# sensor.net
KiCad netlist of a schematic drawn in EAGLE
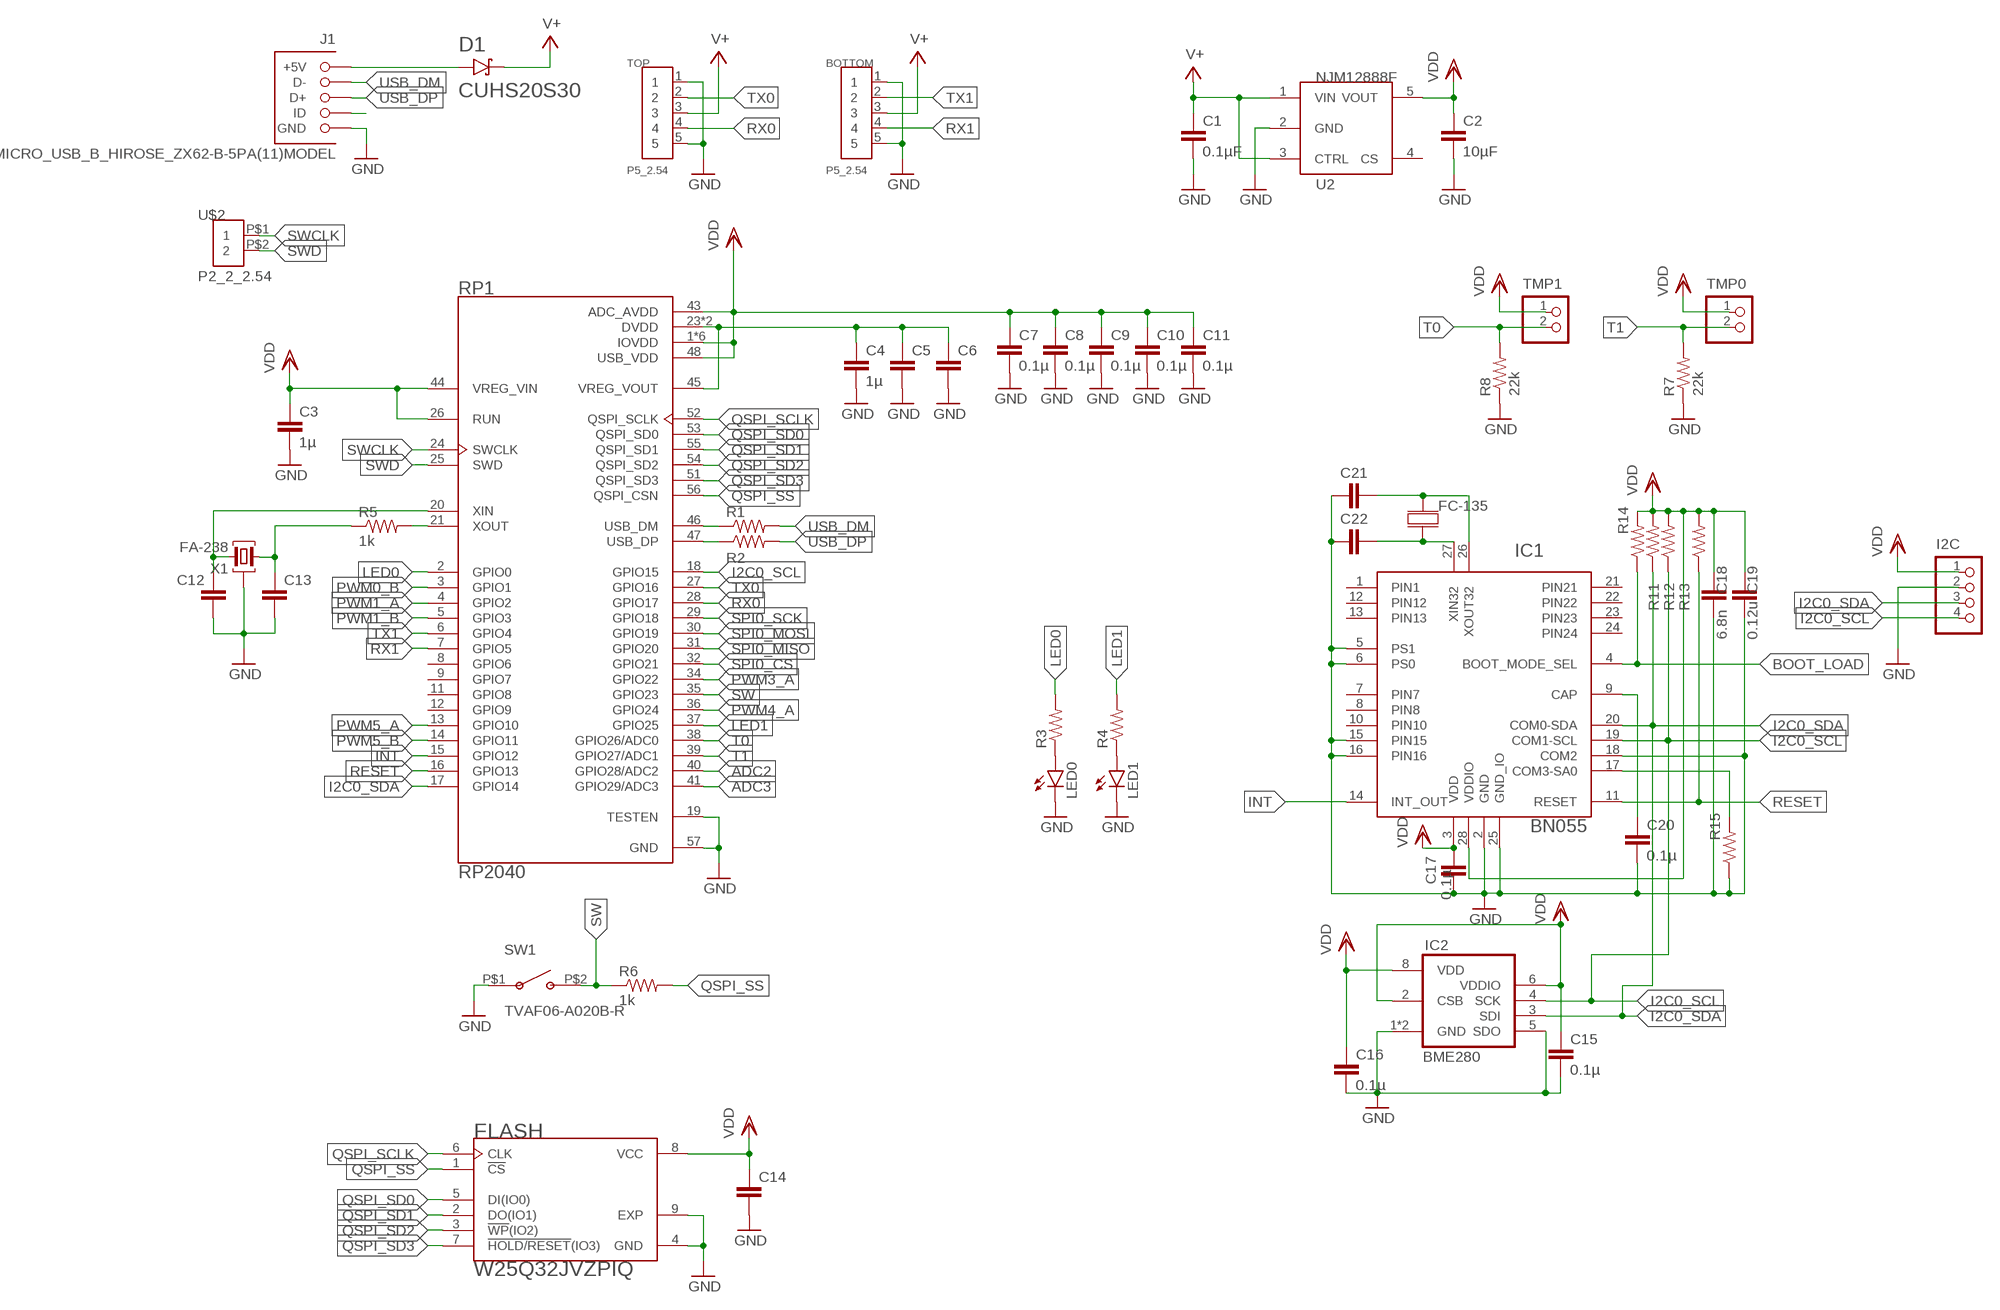
[diagram p0: schematic, sheet 1]

(export (version "E")
  (design (tool "Eeschema 10.0.6"))
  (components
    (comp (ref "BOTTOM")
      (value "P5_2.54")
      (footprint "eagle-import:P5_2.54")
      (libsource (lib "eagle-import") (part "P5_2.54"))
    )
    (comp (ref "C1")
      (value "0.1µF")
      (footprint "eagle-import:C0402")
      (libsource (lib "eagle-import") (part "C-EUC0402"))
    )
    (comp (ref "C2")
      (value "10µF")
      (footprint "eagle-import:C0402")
      (libsource (lib "eagle-import") (part "C-EUC0402"))
    )
    (comp (ref "C3")
      (value "1µ")
      (footprint "eagle-import:C0402")
      (libsource (lib "eagle-import") (part "C-EUC0402"))
    )
    (comp (ref "C4")
      (value "1µ")
      (footprint "eagle-import:C0402")
      (libsource (lib "eagle-import") (part "C-EUC0402"))
    )
    (comp (ref "C5")
      (value "C-EUC0402")
      (footprint "eagle-import:C0402")
      (libsource (lib "eagle-import") (part "C-EUC0402"))
    )
    (comp (ref "C6")
      (value "C-EUC0402")
      (footprint "eagle-import:C0402")
      (libsource (lib "eagle-import") (part "C-EUC0402"))
    )
    (comp (ref "C7")
      (value "0.1µ")
      (footprint "eagle-import:C0402")
      (libsource (lib "eagle-import") (part "C-EUC0402"))
    )
    (comp (ref "C8")
      (value "0.1µ")
      (footprint "eagle-import:C0402")
      (libsource (lib "eagle-import") (part "C-EUC0402"))
    )
    (comp (ref "C9")
      (value "0.1µ")
      (footprint "eagle-import:C0402")
      (libsource (lib "eagle-import") (part "C-EUC0402"))
    )
    (comp (ref "C10")
      (value "0.1µ")
      (footprint "eagle-import:C0402")
      (libsource (lib "eagle-import") (part "C-EUC0402"))
    )
    (comp (ref "C11")
      (value "0.1µ")
      (footprint "eagle-import:C0402")
      (libsource (lib "eagle-import") (part "C-EUC0402"))
    )
    (comp (ref "C12")
      (value "C-EUC0402")
      (footprint "eagle-import:C0402")
      (libsource (lib "eagle-import") (part "C-EUC0402"))
    )
    (comp (ref "C13")
      (value "C-EUC0402")
      (footprint "eagle-import:C0402")
      (libsource (lib "eagle-import") (part "C-EUC0402"))
    )
    (comp (ref "C14")
      (value "C-EUC0402")
      (footprint "eagle-import:C0402")
      (libsource (lib "eagle-import") (part "C-EUC0402"))
    )
    (comp (ref "C15")
      (value "0.1µ")
      (footprint "eagle-import:C0402")
      (libsource (lib "eagle-import") (part "C-EUC0402"))
    )
    (comp (ref "C16")
      (value "0.1µ")
      (footprint "eagle-import:C0402")
      (libsource (lib "eagle-import") (part "C-EUC0402"))
    )
    (comp (ref "C17")
      (value "0.1µ")
      (footprint "eagle-import:C0402")
      (libsource (lib "eagle-import") (part "C-EUC0402"))
    )
    (comp (ref "C18")
      (value "6.8n")
      (footprint "eagle-import:C0402")
      (libsource (lib "eagle-import") (part "C-EUC0402"))
    )
    (comp (ref "C19")
      (value "0.12u")
      (footprint "eagle-import:C0402")
      (libsource (lib "eagle-import") (part "C-EUC0402"))
    )
    (comp (ref "C20")
      (value "0.1µ")
      (footprint "eagle-import:C0402")
      (libsource (lib "eagle-import") (part "C-EUC0402"))
    )
    (comp (ref "C21")
      (value "C-EUC0402")
      (footprint "eagle-import:C0402")
      (libsource (lib "eagle-import") (part "C-EUC0402"))
    )
    (comp (ref "C22")
      (value "C-EUC0402")
      (footprint "eagle-import:C0402")
      (libsource (lib "eagle-import") (part "C-EUC0402"))
    )
    (comp (ref "D1")
      (value "CUHS20S30")
      (footprint "eagle-import:CUHS20S30")
      (libsource (lib "eagle-import") (part "CUHS20S30"))
    )
    (comp (ref "FC-135")
      (value "FC-135")
      (footprint "eagle-import:FC-135")
      (libsource (lib "eagle-import") (part "FC-135"))
    )
    (comp (ref "FLASH")
      (value "W25Q32JVZPIQ")
      (footprint "eagle-import:SON127P600X500X80-9N")
      (fields (field (name "MF") "Winbond"))
      (libsource (lib "eagle-import") (part "W25Q32JVZPIQ"))
    )
    (comp (ref "I2C")
      (value "B4B-PH-K-S")
      (footprint "eagle-import:B4B-PH-K-S")
      (libsource (lib "eagle-import") (part "B4B-PH-K-S"))
    )
    (comp (ref "IC1")
      (value "BN055")
      (footprint "eagle-import:LGA-28_3.80X5.20_0.5")
      (fields (field (name "PART_NUMBER") "BNO055"))
      (libsource (lib "eagle-import") (part "1658_BNO055"))
    )
    (comp (ref "IC2")
      (value "BME280")
      (footprint "eagle-import:BME280")
      (libsource (lib "eagle-import") (part "BME280"))
    )
    (comp (ref "J1")
      (value "MICRO_USB_B_HIROSE_ZX62-B-5PA(11)MODEL")
      (footprint "eagle-import:GHI-CONNECTORS_10118192-0001LF(MICRO-USB-B-AMPHENOL-FCI)")
      (libsource (lib "eagle-import") (part "MICRO_USB_B_HIROSE_ZX62-B-5PA(11)MODEL"))
    )
    (comp (ref "LED0")
      (value "LEDCHIPLED_0603")
      (footprint "eagle-import:CHIPLED_0603")
      (libsource (lib "eagle-import") (part "LEDCHIPLED_0603"))
    )
    (comp (ref "LED1")
      (value "LEDCHIPLED_0603")
      (footprint "eagle-import:CHIPLED_0603")
      (libsource (lib "eagle-import") (part "LEDCHIPLED_0603"))
    )
    (comp (ref "R1")
      (value "R-US_R0402")
      (footprint "eagle-import:R0402")
      (libsource (lib "eagle-import") (part "R-US_R0402"))
    )
    (comp (ref "R2")
      (value "R-US_R0402")
      (footprint "eagle-import:R0402")
      (libsource (lib "eagle-import") (part "R-US_R0402"))
    )
    (comp (ref "R3")
      (value "R-US_R0402")
      (footprint "eagle-import:R0402")
      (libsource (lib "eagle-import") (part "R-US_R0402"))
    )
    (comp (ref "R4")
      (value "R-US_R0402")
      (footprint "eagle-import:R0402")
      (libsource (lib "eagle-import") (part "R-US_R0402"))
    )
    (comp (ref "R5")
      (value "1k")
      (footprint "eagle-import:R0402")
      (libsource (lib "eagle-import") (part "R-US_R0402"))
    )
    (comp (ref "R6")
      (value "1k")
      (footprint "eagle-import:R0402")
      (libsource (lib "eagle-import") (part "R-US_R0402"))
    )
    (comp (ref "R7")
      (value "22k")
      (footprint "eagle-import:R0402")
      (libsource (lib "eagle-import") (part "R-US_R0402"))
    )
    (comp (ref "R8")
      (value "22k")
      (footprint "eagle-import:R0402")
      (libsource (lib "eagle-import") (part "R-US_R0402"))
    )
    (comp (ref "R11")
      (value "R-US_R0402")
      (footprint "eagle-import:R0402")
      (libsource (lib "eagle-import") (part "R-US_R0402"))
    )
    (comp (ref "R12")
      (value "R-US_R0402")
      (footprint "eagle-import:R0402")
      (libsource (lib "eagle-import") (part "R-US_R0402"))
    )
    (comp (ref "R13")
      (value "R-US_R0402")
      (footprint "eagle-import:R0402")
      (libsource (lib "eagle-import") (part "R-US_R0402"))
    )
    (comp (ref "R14")
      (value "R-US_R0402")
      (footprint "eagle-import:R0402")
      (libsource (lib "eagle-import") (part "R-US_R0402"))
    )
    (comp (ref "R15")
      (value "R-US_R0402")
      (footprint "eagle-import:R0402")
      (libsource (lib "eagle-import") (part "R-US_R0402"))
    )
    (comp (ref "RP1")
      (value "RP2040")
      (footprint "eagle-import:QFN40P700X700X90-57N")
      (fields (field (name "MF") "Raspberry Pi"))
      (libsource (lib "eagle-import") (part "RP2040"))
    )
    (comp (ref "SW1")
      (value "TVAF06-A020B-R")
      (footprint "eagle-import:TVAF06-A020B-R")
      (libsource (lib "eagle-import") (part "TVAF06-A020B-R"))
    )
    (comp (ref "TMP0")
      (value "S2B-PH-K-S")
      (footprint "eagle-import:S2B-PH-K-S")
      (libsource (lib "eagle-import") (part "S2B-PH-K-S"))
    )
    (comp (ref "TMP1")
      (value "S2B-PH-K-S")
      (footprint "eagle-import:S2B-PH-K-S")
      (libsource (lib "eagle-import") (part "S2B-PH-K-S"))
    )
    (comp (ref "TOP")
      (value "P5_2.54")
      (footprint "eagle-import:P5_2.54")
      (libsource (lib "eagle-import") (part "P5_2.54"))
    )
    (comp (ref "U$2")
      (value "P2_2_2.54")
      (footprint "eagle-import:P2_2.54")
      (libsource (lib "eagle-import") (part "P2_2_2.54"))
    )
    (comp (ref "U2")
      (value "NJM12888F")
      (footprint "eagle-import:SOT95P240X110-5N")
      (libsource (lib "eagle-import") (part "NJM12888F"))
    )
    (comp (ref "X1")
      (value "FA-238")
      (footprint "eagle-import:FA-238")
      (libsource (lib "eagle-import") (part "FA-238"))
    )
  )
  (nets
    (net (code "1") (name "ADC2") (class "Default")
      (node (ref "RP1") (pin "40") (pinfunction "GPIO28/ADC2_40") (pintype "bidirectional"))
    )
    (net (code "2") (name "ADC3") (class "Default")
      (node (ref "RP1") (pin "41") (pinfunction "GPIO29/ADC3_41") (pintype "bidirectional"))
    )
    (net (code "3") (name "BOOT_LOAD") (class "Default")
      (node (ref "IC1") (pin "4") (pinfunction "BOOT_MODE_SEL_4") (pintype "input"))
      (node (ref "R14") (pin "1") (pinfunction "1_1") (pintype "passive"))
    )
    (net (code "4") (name "GND") (class "Default")
      (node (ref "BOTTOM") (pin "1") (pinfunction "1_1") (pintype "bidirectional"))
      (node (ref "BOTTOM") (pin "5") (pinfunction "5_5") (pintype "bidirectional"))
      (node (ref "C1") (pin "2") (pinfunction "2_2") (pintype "passive"))
      (node (ref "C10") (pin "2") (pinfunction "2_2") (pintype "passive"))
      (node (ref "C11") (pin "2") (pinfunction "2_2") (pintype "passive"))
      (node (ref "C12") (pin "2") (pinfunction "2_2") (pintype "passive"))
      (node (ref "C13") (pin "2") (pinfunction "2_2") (pintype "passive"))
      (node (ref "C14") (pin "2") (pinfunction "2_2") (pintype "passive"))
      (node (ref "C15") (pin "2") (pinfunction "2_2") (pintype "passive"))
      (node (ref "C16") (pin "2") (pinfunction "2_2") (pintype "passive"))
      (node (ref "C17") (pin "2") (pinfunction "2_2") (pintype "passive"))
      (node (ref "C18") (pin "2") (pinfunction "2_2") (pintype "passive"))
      (node (ref "C19") (pin "2") (pinfunction "2_2") (pintype "passive"))
      (node (ref "C2") (pin "2") (pinfunction "2_2") (pintype "passive"))
      (node (ref "C20") (pin "2") (pinfunction "2_2") (pintype "passive"))
      (node (ref "C21") (pin "1") (pinfunction "1_1") (pintype "passive"))
      (node (ref "C22") (pin "1") (pinfunction "1_1") (pintype "passive"))
      (node (ref "C3") (pin "2") (pinfunction "2_2") (pintype "passive"))
      (node (ref "C4") (pin "2") (pinfunction "2_2") (pintype "passive"))
      (node (ref "C5") (pin "2") (pinfunction "2_2") (pintype "passive"))
      (node (ref "C6") (pin "2") (pinfunction "2_2") (pintype "passive"))
      (node (ref "C7") (pin "2") (pinfunction "2_2") (pintype "passive"))
      (node (ref "C8") (pin "2") (pinfunction "2_2") (pintype "passive"))
      (node (ref "C9") (pin "2") (pinfunction "2_2") (pintype "passive"))
      (node (ref "FLASH") (pin "4") (pinfunction "GND_4") (pintype "power_in"))
      (node (ref "FLASH") (pin "9") (pinfunction "EXP_9") (pintype "passive"))
      (node (ref "I2C") (pin "2") (pinfunction "2_2") (pintype "passive"))
      (node (ref "IC1") (pin "15") (pinfunction "PIN15_15") (pintype "passive"))
      (node (ref "IC1") (pin "16") (pinfunction "PIN16_16") (pintype "passive"))
      (node (ref "IC1") (pin "18") (pinfunction "COM2_18") (pintype "bidirectional"))
      (node (ref "IC1") (pin "2") (pinfunction "GND_2") (pintype "power_in"))
      (node (ref "IC1") (pin "25") (pinfunction "GND_IO_25") (pintype "power_in"))
      (node (ref "IC1") (pin "5") (pinfunction "PS1_5") (pintype "input"))
      (node (ref "IC1") (pin "6") (pinfunction "PS0_6") (pintype "input"))
      (node (ref "IC2") (pin "1") (pinfunction "GND_1") (pintype "power_in"))
      (node (ref "IC2") (pin "5") (pinfunction "SDO_5") (pintype "input"))
      (node (ref "IC2") (pin "7") (pinfunction "GND_7") (pintype "power_in"))
      (node (ref "J1") (pin "CGND1") (pinfunction "GND_CGND1") (pintype "bidirectional"))
      (node (ref "J1") (pin "CGND2") (pinfunction "GND_CGND2") (pintype "bidirectional"))
      (node (ref "J1") (pin "CGND3") (pinfunction "GND_CGND3") (pintype "bidirectional"))
      (node (ref "J1") (pin "CGND4") (pinfunction "GND_CGND4") (pintype "bidirectional"))
      (node (ref "J1") (pin "CGND5") (pinfunction "GND_CGND5") (pintype "bidirectional"))
      (node (ref "J1") (pin "CGND6") (pinfunction "GND_CGND6") (pintype "bidirectional"))
      (node (ref "J1") (pin "GND") (pinfunction "GND_GND") (pintype "bidirectional"))
      (node (ref "LED0") (pin "C") (pinfunction "C_C") (pintype "passive"))
      (node (ref "LED1") (pin "C") (pinfunction "C_C") (pintype "passive"))
      (node (ref "R15") (pin "1") (pinfunction "1_1") (pintype "passive"))
      (node (ref "R7") (pin "1") (pinfunction "1_1") (pintype "passive"))
      (node (ref "R8") (pin "1") (pinfunction "1_1") (pintype "passive"))
      (node (ref "RP1") (pin "19") (pinfunction "TESTEN_19") (pintype "passive"))
      (node (ref "RP1") (pin "57") (pinfunction "GND_57") (pintype "power_in"))
      (node (ref "SW1") (pin "P$1") (pinfunction "A_P$1") (pintype "bidirectional"))
      (node (ref "TOP") (pin "1") (pinfunction "1_1") (pintype "bidirectional"))
      (node (ref "TOP") (pin "5") (pinfunction "5_5") (pintype "bidirectional"))
      (node (ref "U2") (pin "2") (pinfunction "GND_2") (pintype "power_in"))
      (node (ref "X1") (pin "2") (pinfunction "G_2") (pintype "passive"))
      (node (ref "X1") (pin "4") (pinfunction "G_4") (pintype "passive"))
    )
    (net (code "5") (name "I2C0_SCL") (class "Default")
      (node (ref "I2C") (pin "4") (pinfunction "4_4") (pintype "passive"))
      (node (ref "IC1") (pin "19") (pinfunction "COM1-SCL_19") (pintype "bidirectional"))
      (node (ref "IC2") (pin "4") (pinfunction "SCK_4") (pintype "bidirectional"))
      (node (ref "R12") (pin "1") (pinfunction "1_1") (pintype "passive"))
      (node (ref "RP1") (pin "18") (pinfunction "GPIO15_18") (pintype "bidirectional"))
    )
    (net (code "6") (name "I2C0_SDA") (class "Default")
      (node (ref "I2C") (pin "3") (pinfunction "3_3") (pintype "passive"))
      (node (ref "IC1") (pin "20") (pinfunction "COM0-SDA_20") (pintype "bidirectional"))
      (node (ref "IC2") (pin "3") (pinfunction "SDI_3") (pintype "bidirectional"))
      (node (ref "R11") (pin "1") (pinfunction "1_1") (pintype "passive"))
      (node (ref "RP1") (pin "17") (pinfunction "GPIO14_17") (pintype "bidirectional"))
    )
    (net (code "7") (name "INT") (class "Default")
      (node (ref "IC1") (pin "14") (pinfunction "INT_OUT_14") (pintype "output"))
      (node (ref "RP1") (pin "15") (pinfunction "GPIO12_15") (pintype "bidirectional"))
    )
    (net (code "8") (name "LED0") (class "Default")
      (node (ref "R3") (pin "2") (pinfunction "2_2") (pintype "passive"))
      (node (ref "RP1") (pin "2") (pinfunction "GPIO0_2") (pintype "bidirectional"))
    )
    (net (code "9") (name "LED1") (class "Default")
      (node (ref "R4") (pin "2") (pinfunction "2_2") (pintype "passive"))
      (node (ref "RP1") (pin "37") (pinfunction "GPIO25_37") (pintype "bidirectional"))
    )
    (net (code "10") (name "Net-(C13-Pad1)") (class "Default")
      (node (ref "C13") (pin "1") (pinfunction "1_1") (pintype "passive"))
      (node (ref "R5") (pin "1") (pinfunction "1_1") (pintype "passive"))
      (node (ref "X1") (pin "1") (pinfunction "1_1") (pintype "passive"))
    )
    (net (code "11") (name "Net-(IC1-CAP)") (class "Default")
      (node (ref "C20") (pin "1") (pinfunction "1_1") (pintype "passive"))
      (node (ref "IC1") (pin "9") (pinfunction "CAP_9") (pintype "tri_state"))
    )
    (net (code "12") (name "Net-(IC1-COM3-SA0)") (class "Default")
      (node (ref "IC1") (pin "17") (pinfunction "COM3-SA0_17") (pintype "bidirectional"))
      (node (ref "R15") (pin "2") (pinfunction "2_2") (pintype "passive"))
    )
    (net (code "13") (name "Net-(IC1-XIN32)") (class "Default")
      (node (ref "C22") (pin "2") (pinfunction "2_2") (pintype "passive"))
      (node (ref "FC-135") (pin "P$2") (pinfunction "P$2_P$2") (pintype "bidirectional"))
      (node (ref "IC1") (pin "27") (pinfunction "XIN32_27") (pintype "bidirectional"))
    )
    (net (code "14") (name "Net-(IC1-XOUT32)") (class "Default")
      (node (ref "C21") (pin "2") (pinfunction "2_2") (pintype "passive"))
      (node (ref "FC-135") (pin "P$1") (pinfunction "P$1_P$1") (pintype "bidirectional"))
      (node (ref "IC1") (pin "26") (pinfunction "XOUT32_26") (pintype "output"))
    )
    (net (code "15") (name "Net-(J1-+5V)") (class "Default")
      (node (ref "D1") (pin "A") (pinfunction "A_A") (pintype "bidirectional"))
      (node (ref "J1") (pin "VBUS") (pinfunction "+5V_VBUS") (pintype "bidirectional"))
    )
    (net (code "16") (name "Net-(LED0-PadA)") (class "Default")
      (node (ref "LED0") (pin "A") (pinfunction "A_A") (pintype "passive"))
      (node (ref "R3") (pin "1") (pinfunction "1_1") (pintype "passive"))
    )
    (net (code "17") (name "Net-(LED1-PadA)") (class "Default")
      (node (ref "LED1") (pin "A") (pinfunction "A_A") (pintype "passive"))
      (node (ref "R4") (pin "1") (pinfunction "1_1") (pintype "passive"))
    )
    (net (code "18") (name "Net-(RP1-USB_DM)") (class "Default")
      (node (ref "R1") (pin "1") (pinfunction "1_1") (pintype "passive"))
      (node (ref "RP1") (pin "46") (pinfunction "USB_DM_46") (pintype "bidirectional"))
    )
    (net (code "19") (name "Net-(RP1-USB_DP)") (class "Default")
      (node (ref "R2") (pin "1") (pinfunction "1_1") (pintype "passive"))
      (node (ref "RP1") (pin "47") (pinfunction "USB_DP_47") (pintype "bidirectional"))
    )
    (net (code "20") (name "Net-(RP1-VREG_VOUT)") (class "Default")
      (node (ref "C4") (pin "1") (pinfunction "1_1") (pintype "passive"))
      (node (ref "C5") (pin "1") (pinfunction "1_1") (pintype "passive"))
      (node (ref "C6") (pin "1") (pinfunction "1_1") (pintype "passive"))
      (node (ref "RP1") (pin "23") (pinfunction "DVDD_23") (pintype "power_in"))
      (node (ref "RP1") (pin "45") (pinfunction "VREG_VOUT_45") (pintype "output"))
      (node (ref "RP1") (pin "50") (pinfunction "DVDD_50") (pintype "power_in"))
    )
    (net (code "21") (name "Net-(RP1-XIN)") (class "Default")
      (node (ref "C12") (pin "1") (pinfunction "1_1") (pintype "passive"))
      (node (ref "RP1") (pin "20") (pinfunction "XIN_20") (pintype "input"))
      (node (ref "X1") (pin "3") (pinfunction "2_3") (pintype "passive"))
    )
    (net (code "22") (name "Net-(RP1-XOUT)") (class "Default")
      (node (ref "R5") (pin "2") (pinfunction "2_2") (pintype "passive"))
      (node (ref "RP1") (pin "21") (pinfunction "XOUT_21") (pintype "output"))
    )
    (net (code "23") (name "PWM0_B") (class "Default")
      (node (ref "RP1") (pin "3") (pinfunction "GPIO1_3") (pintype "bidirectional"))
    )
    (net (code "24") (name "PWM1_A") (class "Default")
      (node (ref "RP1") (pin "4") (pinfunction "GPIO2_4") (pintype "bidirectional"))
    )
    (net (code "25") (name "PWM1_B") (class "Default")
      (node (ref "RP1") (pin "5") (pinfunction "GPIO3_5") (pintype "bidirectional"))
    )
    (net (code "26") (name "PWM3_A") (class "Default")
      (node (ref "RP1") (pin "34") (pinfunction "GPIO22_34") (pintype "bidirectional"))
    )
    (net (code "27") (name "PWM4_A") (class "Default")
      (node (ref "RP1") (pin "36") (pinfunction "GPIO24_36") (pintype "bidirectional"))
    )
    (net (code "28") (name "PWM5_A") (class "Default")
      (node (ref "RP1") (pin "13") (pinfunction "GPIO10_13") (pintype "bidirectional"))
    )
    (net (code "29") (name "PWM5_B") (class "Default")
      (node (ref "RP1") (pin "14") (pinfunction "GPIO11_14") (pintype "bidirectional"))
    )
    (net (code "30") (name "QSPI_SCLK") (class "Default")
      (node (ref "FLASH") (pin "6") (pinfunction "CLK_6") (pintype "input"))
      (node (ref "RP1") (pin "52") (pinfunction "QSPI_SCLK_52") (pintype "bidirectional"))
    )
    (net (code "31") (name "QSPI_SD0") (class "Default")
      (node (ref "FLASH") (pin "5") (pinfunction "DI(IO0)_5") (pintype "bidirectional"))
      (node (ref "RP1") (pin "53") (pinfunction "QSPI_SD0_53") (pintype "bidirectional"))
    )
    (net (code "32") (name "QSPI_SD1") (class "Default")
      (node (ref "FLASH") (pin "2") (pinfunction "DO(IO1)_2") (pintype "bidirectional"))
      (node (ref "RP1") (pin "55") (pinfunction "QSPI_SD1_55") (pintype "bidirectional"))
    )
    (net (code "33") (name "QSPI_SD2") (class "Default")
      (node (ref "FLASH") (pin "3") (pinfunction "~{WP}(IO2)_3") (pintype "bidirectional"))
      (node (ref "RP1") (pin "54") (pinfunction "QSPI_SD2_54") (pintype "bidirectional"))
    )
    (net (code "34") (name "QSPI_SD3") (class "Default")
      (node (ref "FLASH") (pin "7") (pinfunction "~{HOLD/RESET}(IO3)_7") (pintype "bidirectional"))
      (node (ref "RP1") (pin "51") (pinfunction "QSPI_SD3_51") (pintype "bidirectional"))
    )
    (net (code "35") (name "QSPI_SS") (class "Default")
      (node (ref "FLASH") (pin "1") (pinfunction "~{CS}_1") (pintype "input"))
      (node (ref "R6") (pin "2") (pinfunction "2_2") (pintype "passive"))
      (node (ref "RP1") (pin "56") (pinfunction "QSPI_CSN_56") (pintype "bidirectional"))
    )
    (net (code "36") (name "RESET") (class "Default")
      (node (ref "IC1") (pin "11") (pinfunction "RESET_11") (pintype "input"))
      (node (ref "R13") (pin "1") (pinfunction "1_1") (pintype "passive"))
      (node (ref "RP1") (pin "16") (pinfunction "GPIO13_16") (pintype "bidirectional"))
    )
    (net (code "37") (name "RX0") (class "Default")
      (node (ref "RP1") (pin "28") (pinfunction "GPIO17_28") (pintype "bidirectional"))
      (node (ref "TOP") (pin "4") (pinfunction "4_4") (pintype "bidirectional"))
    )
    (net (code "38") (name "RX1") (class "Default")
      (node (ref "BOTTOM") (pin "4") (pinfunction "4_4") (pintype "bidirectional"))
      (node (ref "RP1") (pin "7") (pinfunction "GPIO5_7") (pintype "bidirectional"))
    )
    (net (code "39") (name "SPI0_CS") (class "Default")
      (node (ref "RP1") (pin "32") (pinfunction "GPIO21_32") (pintype "bidirectional"))
    )
    (net (code "40") (name "SPI0_MISO") (class "Default")
      (node (ref "RP1") (pin "31") (pinfunction "GPIO20_31") (pintype "bidirectional"))
    )
    (net (code "41") (name "SPI0_MOSI") (class "Default")
      (node (ref "RP1") (pin "30") (pinfunction "GPIO19_30") (pintype "bidirectional"))
    )
    (net (code "42") (name "SPI0_SCK") (class "Default")
      (node (ref "RP1") (pin "29") (pinfunction "GPIO18_29") (pintype "bidirectional"))
    )
    (net (code "43") (name "SW") (class "Default")
      (node (ref "R6") (pin "1") (pinfunction "1_1") (pintype "passive"))
      (node (ref "RP1") (pin "35") (pinfunction "GPIO23_35") (pintype "bidirectional"))
      (node (ref "SW1") (pin "P$2") (pinfunction "B_P$2") (pintype "bidirectional"))
    )
    (net (code "44") (name "SWCLK") (class "Default")
      (node (ref "RP1") (pin "24") (pinfunction "SWCLK_24") (pintype "input"))
      (node (ref "U$2") (pin "P$1") (pinfunction "1_P$1") (pintype "bidirectional"))
    )
    (net (code "45") (name "SWD") (class "Default")
      (node (ref "RP1") (pin "25") (pinfunction "SWD_25") (pintype "bidirectional"))
      (node (ref "U$2") (pin "P$2") (pinfunction "2_P$2") (pintype "bidirectional"))
    )
    (net (code "46") (name "T0") (class "Default")
      (node (ref "R8") (pin "2") (pinfunction "2_2") (pintype "passive"))
      (node (ref "RP1") (pin "38") (pinfunction "GPIO26/ADC0_38") (pintype "bidirectional"))
      (node (ref "TMP1") (pin "2") (pinfunction "2_2") (pintype "passive"))
    )
    (net (code "47") (name "T1") (class "Default")
      (node (ref "R7") (pin "2") (pinfunction "2_2") (pintype "passive"))
      (node (ref "RP1") (pin "39") (pinfunction "GPIO27/ADC1_39") (pintype "bidirectional"))
      (node (ref "TMP0") (pin "2") (pinfunction "2_2") (pintype "passive"))
    )
    (net (code "48") (name "TX0") (class "Default")
      (node (ref "RP1") (pin "27") (pinfunction "GPIO16_27") (pintype "bidirectional"))
      (node (ref "TOP") (pin "2") (pinfunction "2_2") (pintype "bidirectional"))
    )
    (net (code "49") (name "TX1") (class "Default")
      (node (ref "BOTTOM") (pin "2") (pinfunction "2_2") (pintype "bidirectional"))
      (node (ref "RP1") (pin "6") (pinfunction "GPIO4_6") (pintype "bidirectional"))
    )
    (net (code "50") (name "USB_DM") (class "Default")
      (node (ref "J1") (pin "D-") (pinfunction "D-_D-") (pintype "bidirectional"))
      (node (ref "R1") (pin "2") (pinfunction "2_2") (pintype "passive"))
    )
    (net (code "51") (name "USB_DP") (class "Default")
      (node (ref "J1") (pin "D+") (pinfunction "D+_D+") (pintype "bidirectional"))
      (node (ref "R2") (pin "2") (pinfunction "2_2") (pintype "passive"))
    )
    (net (code "52") (name "V+") (class "Default")
      (node (ref "BOTTOM") (pin "3") (pinfunction "3_3") (pintype "bidirectional"))
      (node (ref "C1") (pin "1") (pinfunction "1_1") (pintype "passive"))
      (node (ref "D1") (pin "C") (pinfunction "C_C") (pintype "bidirectional"))
      (node (ref "TOP") (pin "3") (pinfunction "3_3") (pintype "bidirectional"))
      (node (ref "U2") (pin "1") (pinfunction "VIN_1") (pintype "power_in"))
      (node (ref "U2") (pin "3") (pinfunction "CTRL_3") (pintype "input"))
    )
    (net (code "53") (name "VDD") (class "Default")
      (node (ref "C10") (pin "1") (pinfunction "1_1") (pintype "passive"))
      (node (ref "C11") (pin "1") (pinfunction "1_1") (pintype "passive"))
      (node (ref "C14") (pin "1") (pinfunction "1_1") (pintype "passive"))
      (node (ref "C15") (pin "1") (pinfunction "1_1") (pintype "passive"))
      (node (ref "C16") (pin "1") (pinfunction "1_1") (pintype "passive"))
      (node (ref "C17") (pin "1") (pinfunction "1_1") (pintype "passive"))
      (node (ref "C18") (pin "1") (pinfunction "1_1") (pintype "passive"))
      (node (ref "C19") (pin "1") (pinfunction "1_1") (pintype "passive"))
      (node (ref "C2") (pin "1") (pinfunction "1_1") (pintype "passive"))
      (node (ref "C3") (pin "1") (pinfunction "1_1") (pintype "passive"))
      (node (ref "C7") (pin "1") (pinfunction "1_1") (pintype "passive"))
      (node (ref "C8") (pin "1") (pinfunction "1_1") (pintype "passive"))
      (node (ref "C9") (pin "1") (pinfunction "1_1") (pintype "passive"))
      (node (ref "FLASH") (pin "8") (pinfunction "VCC_8") (pintype "power_in"))
      (node (ref "I2C") (pin "1") (pinfunction "1_1") (pintype "passive"))
      (node (ref "IC1") (pin "28") (pinfunction "VDDIO_28") (pintype "power_in"))
      (node (ref "IC1") (pin "3") (pinfunction "VDD_3") (pintype "power_in"))
      (node (ref "IC2") (pin "2") (pinfunction "CSB_2") (pintype "input"))
      (node (ref "IC2") (pin "6") (pinfunction "VDDIO_6") (pintype "power_in"))
      (node (ref "IC2") (pin "8") (pinfunction "VDD_8") (pintype "power_in"))
      (node (ref "R11") (pin "2") (pinfunction "2_2") (pintype "passive"))
      (node (ref "R12") (pin "2") (pinfunction "2_2") (pintype "passive"))
      (node (ref "R13") (pin "2") (pinfunction "2_2") (pintype "passive"))
      (node (ref "R14") (pin "2") (pinfunction "2_2") (pintype "passive"))
      (node (ref "RP1") (pin "1") (pinfunction "IOVDD_1") (pintype "power_in"))
      (node (ref "RP1") (pin "10") (pinfunction "IOVDD_10") (pintype "power_in"))
      (node (ref "RP1") (pin "22") (pinfunction "IOVDD_22") (pintype "power_in"))
      (node (ref "RP1") (pin "26") (pinfunction "RUN_26") (pintype "input"))
      (node (ref "RP1") (pin "33") (pinfunction "IOVDD_33") (pintype "power_in"))
      (node (ref "RP1") (pin "42") (pinfunction "IOVDD_42") (pintype "power_in"))
      (node (ref "RP1") (pin "43") (pinfunction "ADC_AVDD_43") (pintype "power_in"))
      (node (ref "RP1") (pin "44") (pinfunction "VREG_VIN_44") (pintype "input"))
      (node (ref "RP1") (pin "48") (pinfunction "USB_VDD_48") (pintype "power_in"))
      (node (ref "RP1") (pin "49") (pinfunction "IOVDD_49") (pintype "power_in"))
      (node (ref "TMP0") (pin "1") (pinfunction "1_1") (pintype "passive"))
      (node (ref "TMP1") (pin "1") (pinfunction "1_1") (pintype "passive"))
      (node (ref "U2") (pin "5") (pinfunction "VOUT_5") (pintype "power_in"))
    )
    (net (code "54") (name "unconnected-(IC1-PIN1-Pad1)") (class "Default")
      (node (ref "IC1") (pin "1") (pinfunction "PIN1_1") (pintype "no_connect"))
    )
    (net (code "55") (name "unconnected-(IC1-PIN7-Pad7)") (class "Default")
      (node (ref "IC1") (pin "7") (pinfunction "PIN7_7") (pintype "tri_state"))
    )
    (net (code "56") (name "unconnected-(IC1-PIN8-Pad8)") (class "Default")
      (node (ref "IC1") (pin "8") (pinfunction "PIN8_8") (pintype "tri_state"))
    )
    (net (code "57") (name "unconnected-(IC1-PIN10-Pad10)") (class "Default")
      (node (ref "IC1") (pin "10") (pinfunction "PIN10_10") (pintype "passive"))
    )
    (net (code "58") (name "unconnected-(IC1-PIN12-Pad12)") (class "Default")
      (node (ref "IC1") (pin "12") (pinfunction "PIN12_12") (pintype "passive"))
    )
    (net (code "59") (name "unconnected-(IC1-PIN13-Pad13)") (class "Default")
      (node (ref "IC1") (pin "13") (pinfunction "PIN13_13") (pintype "passive"))
    )
    (net (code "60") (name "unconnected-(IC1-PIN21-Pad21)") (class "Default")
      (node (ref "IC1") (pin "21") (pinfunction "PIN21_21") (pintype "passive"))
    )
    (net (code "61") (name "unconnected-(IC1-PIN22-Pad22)") (class "Default")
      (node (ref "IC1") (pin "22") (pinfunction "PIN22_22") (pintype "passive"))
    )
    (net (code "62") (name "unconnected-(IC1-PIN23-Pad23)") (class "Default")
      (node (ref "IC1") (pin "23") (pinfunction "PIN23_23") (pintype "passive"))
    )
    (net (code "63") (name "unconnected-(IC1-PIN24-Pad24)") (class "Default")
      (node (ref "IC1") (pin "24") (pinfunction "PIN24_24") (pintype "passive"))
    )
    (net (code "64") (name "unconnected-(J1-PadID)") (class "Default")
      (node (ref "J1") (pin "ID") (pinfunction "ID_ID") (pintype "bidirectional"))
    )
    (net (code "65") (name "unconnected-(RP1-GPIO6-Pad8)") (class "Default")
      (node (ref "RP1") (pin "8") (pinfunction "GPIO6_8") (pintype "bidirectional"))
    )
    (net (code "66") (name "unconnected-(RP1-GPIO7-Pad9)") (class "Default")
      (node (ref "RP1") (pin "9") (pinfunction "GPIO7_9") (pintype "bidirectional"))
    )
    (net (code "67") (name "unconnected-(RP1-GPIO8-Pad11)") (class "Default")
      (node (ref "RP1") (pin "11") (pinfunction "GPIO8_11") (pintype "bidirectional"))
    )
    (net (code "68") (name "unconnected-(RP1-GPIO9-Pad12)") (class "Default")
      (node (ref "RP1") (pin "12") (pinfunction "GPIO9_12") (pintype "bidirectional"))
    )
    (net (code "69") (name "unconnected-(U2-CS-Pad4)") (class "Default")
      (node (ref "U2") (pin "4") (pinfunction "CS_4") (pintype "input"))
    )
  )
)
